# MultiSensor_MPL.net
KiCad netlist of a schematic drawn in EAGLE
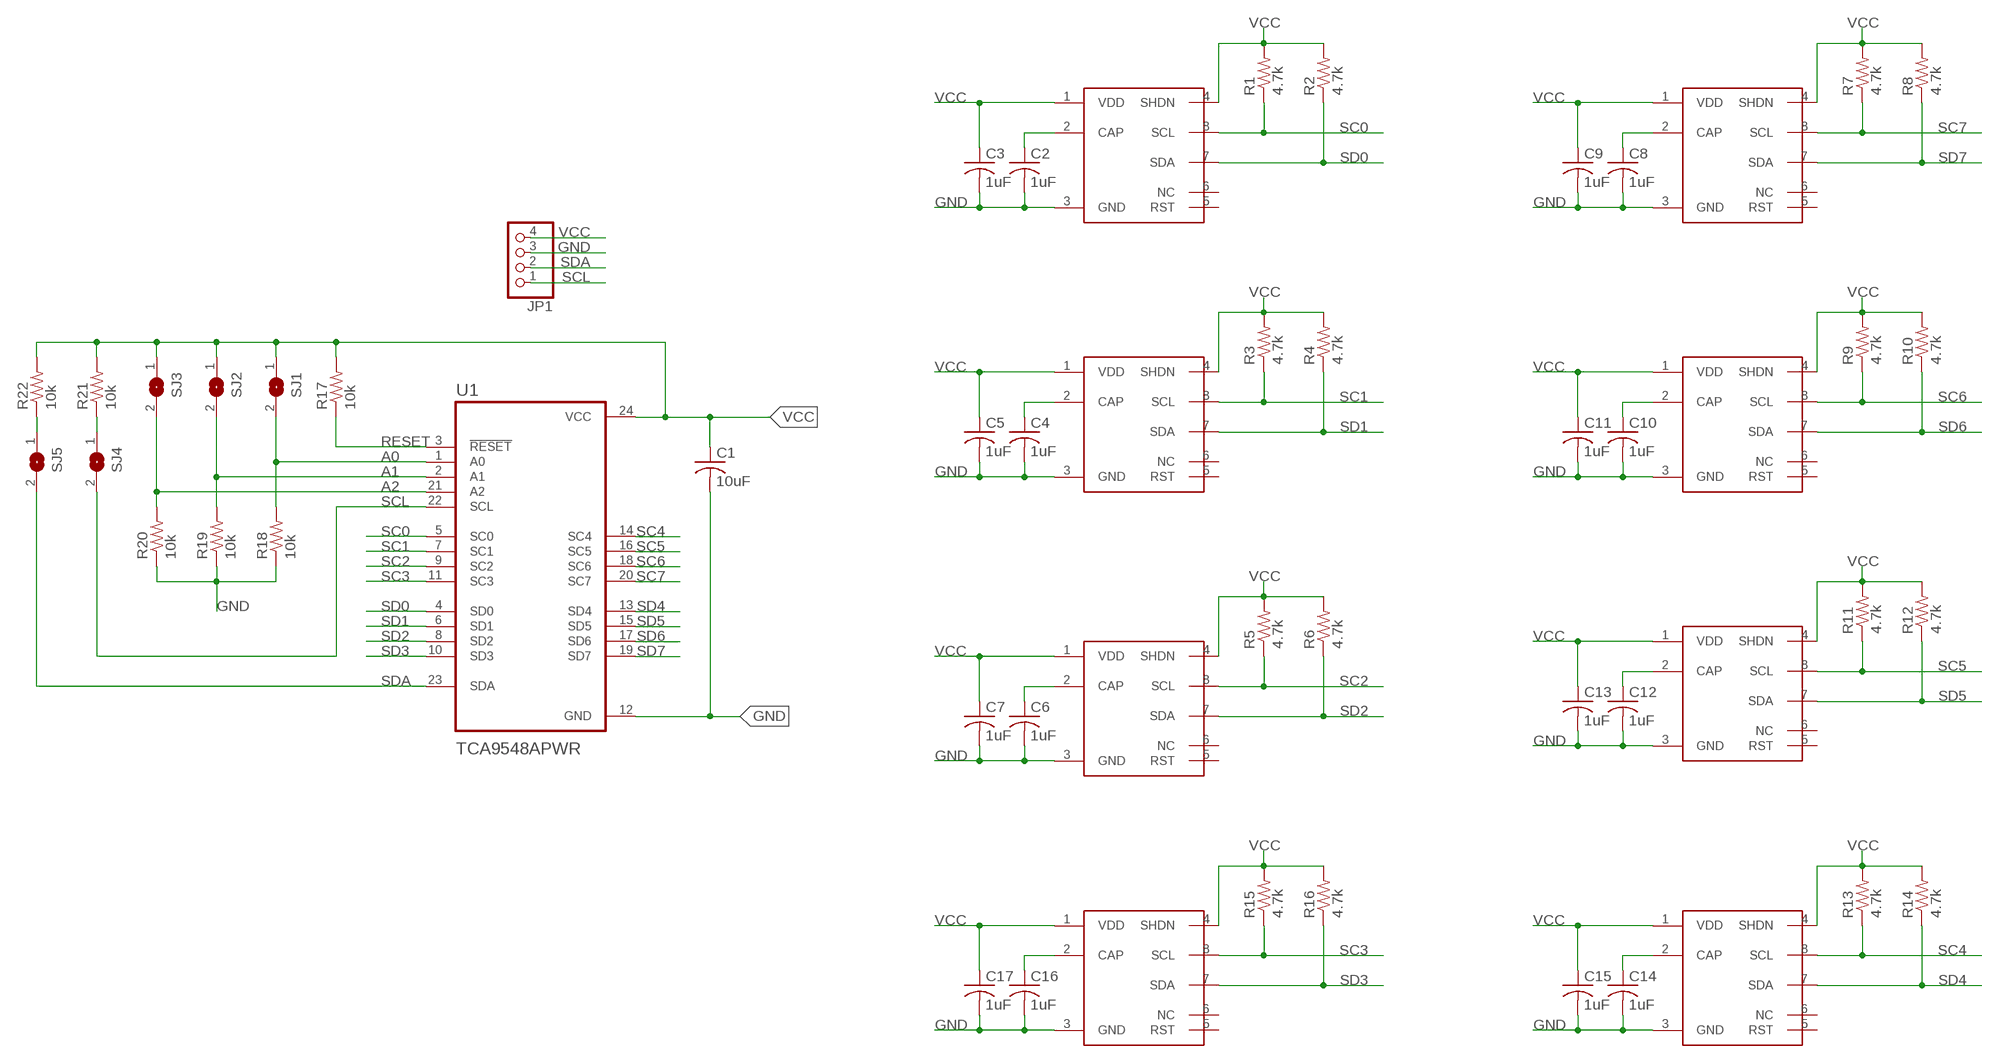
[diagram p0: schematic, sheet 1]

(export (version "E")
  (design (tool "Eeschema 10.0.6"))
  (components
    (comp (ref "B1")
      (value "MPL115A2T1")
      (footprint "eagle-import:MPL115A2T1")
      (libsource (lib "eagle-import") (part "MPL115A2T1"))
    )
    (comp (ref "B2")
      (value "MPL115A2T1")
      (footprint "eagle-import:MPL115A2T1")
      (libsource (lib "eagle-import") (part "MPL115A2T1"))
    )
    (comp (ref "B3")
      (value "MPL115A2T1")
      (footprint "eagle-import:MPL115A2T1")
      (libsource (lib "eagle-import") (part "MPL115A2T1"))
    )
    (comp (ref "B4")
      (value "MPL115A2T1")
      (footprint "eagle-import:MPL115A2T1")
      (libsource (lib "eagle-import") (part "MPL115A2T1"))
    )
    (comp (ref "B5")
      (value "MPL115A2T1")
      (footprint "eagle-import:MPL115A2T1")
      (libsource (lib "eagle-import") (part "MPL115A2T1"))
    )
    (comp (ref "B6")
      (value "MPL115A2T1")
      (footprint "eagle-import:MPL115A2T1")
      (libsource (lib "eagle-import") (part "MPL115A2T1"))
    )
    (comp (ref "B7")
      (value "MPL115A2T1")
      (footprint "eagle-import:MPL115A2T1")
      (libsource (lib "eagle-import") (part "MPL115A2T1"))
    )
    (comp (ref "B8")
      (value "MPL115A2T1")
      (footprint "eagle-import:MPL115A2T1")
      (libsource (lib "eagle-import") (part "MPL115A2T1"))
    )
    (comp (ref "C1")
      (value "10uF")
      (footprint "eagle-import:C0805")
      (libsource (lib "eagle-import") (part "C-USC0805"))
    )
    (comp (ref "C2")
      (value "1uF")
      (footprint "eagle-import:C0805")
      (libsource (lib "eagle-import") (part "C-USC0805"))
    )
    (comp (ref "C3")
      (value "1uF")
      (footprint "eagle-import:C0805")
      (libsource (lib "eagle-import") (part "C-USC0805"))
    )
    (comp (ref "C4")
      (value "1uF")
      (footprint "eagle-import:C0805")
      (libsource (lib "eagle-import") (part "C-USC0805"))
    )
    (comp (ref "C5")
      (value "1uF")
      (footprint "eagle-import:C0805")
      (libsource (lib "eagle-import") (part "C-USC0805"))
    )
    (comp (ref "C6")
      (value "1uF")
      (footprint "eagle-import:C0805")
      (libsource (lib "eagle-import") (part "C-USC0805"))
    )
    (comp (ref "C7")
      (value "1uF")
      (footprint "eagle-import:C0805")
      (libsource (lib "eagle-import") (part "C-USC0805"))
    )
    (comp (ref "C8")
      (value "1uF")
      (footprint "eagle-import:C0805")
      (libsource (lib "eagle-import") (part "C-USC0805"))
    )
    (comp (ref "C9")
      (value "1uF")
      (footprint "eagle-import:C0805")
      (libsource (lib "eagle-import") (part "C-USC0805"))
    )
    (comp (ref "C10")
      (value "1uF")
      (footprint "eagle-import:C0805")
      (libsource (lib "eagle-import") (part "C-USC0805"))
    )
    (comp (ref "C11")
      (value "1uF")
      (footprint "eagle-import:C0805")
      (libsource (lib "eagle-import") (part "C-USC0805"))
    )
    (comp (ref "C12")
      (value "1uF")
      (footprint "eagle-import:C0805")
      (libsource (lib "eagle-import") (part "C-USC0805"))
    )
    (comp (ref "C13")
      (value "1uF")
      (footprint "eagle-import:C0805")
      (libsource (lib "eagle-import") (part "C-USC0805"))
    )
    (comp (ref "C14")
      (value "1uF")
      (footprint "eagle-import:C0805")
      (libsource (lib "eagle-import") (part "C-USC0805"))
    )
    (comp (ref "C15")
      (value "1uF")
      (footprint "eagle-import:C0805")
      (libsource (lib "eagle-import") (part "C-USC0805"))
    )
    (comp (ref "C16")
      (value "1uF")
      (footprint "eagle-import:C0805")
      (libsource (lib "eagle-import") (part "C-USC0805"))
    )
    (comp (ref "C17")
      (value "1uF")
      (footprint "eagle-import:C0805")
      (libsource (lib "eagle-import") (part "C-USC0805"))
    )
    (comp (ref "JP1")
      (value "PINHD-1X4")
      (footprint "eagle-import:1X04")
      (libsource (lib "eagle-import") (part "PINHD-1X4"))
    )
    (comp (ref "R1")
      (value "4.7k")
      (footprint "eagle-import:R0805")
      (libsource (lib "eagle-import") (part "R-US_R0805"))
    )
    (comp (ref "R2")
      (value "4.7k")
      (footprint "eagle-import:R0805")
      (libsource (lib "eagle-import") (part "R-US_R0805"))
    )
    (comp (ref "R3")
      (value "4.7k")
      (footprint "eagle-import:R0805")
      (libsource (lib "eagle-import") (part "R-US_R0805"))
    )
    (comp (ref "R4")
      (value "4.7k")
      (footprint "eagle-import:R0805")
      (libsource (lib "eagle-import") (part "R-US_R0805"))
    )
    (comp (ref "R5")
      (value "4.7k")
      (footprint "eagle-import:R0805")
      (libsource (lib "eagle-import") (part "R-US_R0805"))
    )
    (comp (ref "R6")
      (value "4.7k")
      (footprint "eagle-import:R0805")
      (libsource (lib "eagle-import") (part "R-US_R0805"))
    )
    (comp (ref "R7")
      (value "4.7k")
      (footprint "eagle-import:R0805")
      (libsource (lib "eagle-import") (part "R-US_R0805"))
    )
    (comp (ref "R8")
      (value "4.7k")
      (footprint "eagle-import:R0805")
      (libsource (lib "eagle-import") (part "R-US_R0805"))
    )
    (comp (ref "R9")
      (value "4.7k")
      (footprint "eagle-import:R0805")
      (libsource (lib "eagle-import") (part "R-US_R0805"))
    )
    (comp (ref "R10")
      (value "4.7k")
      (footprint "eagle-import:R0805")
      (libsource (lib "eagle-import") (part "R-US_R0805"))
    )
    (comp (ref "R11")
      (value "4.7k")
      (footprint "eagle-import:R0805")
      (libsource (lib "eagle-import") (part "R-US_R0805"))
    )
    (comp (ref "R12")
      (value "4.7k")
      (footprint "eagle-import:R0805")
      (libsource (lib "eagle-import") (part "R-US_R0805"))
    )
    (comp (ref "R13")
      (value "4.7k")
      (footprint "eagle-import:R0805")
      (libsource (lib "eagle-import") (part "R-US_R0805"))
    )
    (comp (ref "R14")
      (value "4.7k")
      (footprint "eagle-import:R0805")
      (libsource (lib "eagle-import") (part "R-US_R0805"))
    )
    (comp (ref "R15")
      (value "4.7k")
      (footprint "eagle-import:R0805")
      (libsource (lib "eagle-import") (part "R-US_R0805"))
    )
    (comp (ref "R16")
      (value "4.7k")
      (footprint "eagle-import:R0805")
      (libsource (lib "eagle-import") (part "R-US_R0805"))
    )
    (comp (ref "R17")
      (value "10k")
      (footprint "eagle-import:R0805")
      (libsource (lib "eagle-import") (part "resistor_348_R-US_R0805"))
    )
    (comp (ref "R18")
      (value "10k")
      (footprint "eagle-import:R0805")
      (libsource (lib "eagle-import") (part "resistor_348_R-US_R0805"))
    )
    (comp (ref "R19")
      (value "10k")
      (footprint "eagle-import:R0805")
      (libsource (lib "eagle-import") (part "resistor_348_R-US_R0805"))
    )
    (comp (ref "R20")
      (value "10k")
      (footprint "eagle-import:R0805")
      (libsource (lib "eagle-import") (part "resistor_348_R-US_R0805"))
    )
    (comp (ref "R21")
      (value "10k")
      (footprint "eagle-import:R0805")
      (libsource (lib "eagle-import") (part "resistor_348_R-US_R0805"))
    )
    (comp (ref "R22")
      (value "10k")
      (footprint "eagle-import:R0805")
      (libsource (lib "eagle-import") (part "resistor_348_R-US_R0805"))
    )
    (comp (ref "SJ1") (value "SJ") (footprint "eagle-import:SJ") (libsource (lib "eagle-import") (part "SJ")))
    (comp (ref "SJ2") (value "SJ") (footprint "eagle-import:SJ") (libsource (lib "eagle-import") (part "SJ")))
    (comp (ref "SJ3") (value "SJ") (footprint "eagle-import:SJ") (libsource (lib "eagle-import") (part "SJ")))
    (comp (ref "SJ4") (value "SJ") (footprint "eagle-import:SJ") (libsource (lib "eagle-import") (part "SJ")))
    (comp (ref "SJ5") (value "SJ") (footprint "eagle-import:SJ") (libsource (lib "eagle-import") (part "SJ")))
    (comp (ref "U1")
      (value "TCA9548APWR")
      (footprint "eagle-import:SOP65P640X120-24N")
      (fields (field (name "DIGI-KEY_PART_NUMBER") "296-34905-1-ND") (field (name "MF") "Texas Instruments"))
      (libsource (lib "eagle-import") (part "TCA9548APWR"))
    )
  )
  (nets
    (net (code "1") (name "/A0") (class "Default")
      (node (ref "R18") (pin "2") (pinfunction "2_2") (pintype "passive"))
      (node (ref "SJ1") (pin "2") (pinfunction "2_2") (pintype "passive"))
      (node (ref "U1") (pin "1") (pinfunction "A0_1") (pintype "input"))
    )
    (net (code "2") (name "/A1") (class "Default")
      (node (ref "R19") (pin "2") (pinfunction "2_2") (pintype "passive"))
      (node (ref "SJ2") (pin "2") (pinfunction "2_2") (pintype "passive"))
      (node (ref "U1") (pin "2") (pinfunction "A1_2") (pintype "input"))
    )
    (net (code "3") (name "/A2") (class "Default")
      (node (ref "R20") (pin "2") (pinfunction "2_2") (pintype "passive"))
      (node (ref "SJ3") (pin "2") (pinfunction "2_2") (pintype "passive"))
      (node (ref "U1") (pin "21") (pinfunction "A2_21") (pintype "input"))
    )
    (net (code "4") (name "/RESET") (class "Default")
      (node (ref "R17") (pin "1") (pinfunction "1_1") (pintype "passive"))
      (node (ref "U1") (pin "3") (pinfunction "~{RESET}_3") (pintype "input"))
    )
    (net (code "5") (name "/SC0") (class "Default")
      (node (ref "B1") (pin "8") (pinfunction "SCL_8") (pintype "bidirectional"))
      (node (ref "R1") (pin "1") (pinfunction "1_1") (pintype "passive"))
      (node (ref "U1") (pin "5") (pinfunction "SC0_5") (pintype "bidirectional"))
    )
    (net (code "6") (name "/SC1") (class "Default")
      (node (ref "B2") (pin "8") (pinfunction "SCL_8") (pintype "bidirectional"))
      (node (ref "R3") (pin "1") (pinfunction "1_1") (pintype "passive"))
      (node (ref "U1") (pin "7") (pinfunction "SC1_7") (pintype "bidirectional"))
    )
    (net (code "7") (name "/SC2") (class "Default")
      (node (ref "B3") (pin "8") (pinfunction "SCL_8") (pintype "bidirectional"))
      (node (ref "R5") (pin "1") (pinfunction "1_1") (pintype "passive"))
      (node (ref "U1") (pin "9") (pinfunction "SC2_9") (pintype "bidirectional"))
    )
    (net (code "8") (name "/SC3") (class "Default")
      (node (ref "B8") (pin "8") (pinfunction "SCL_8") (pintype "bidirectional"))
      (node (ref "R15") (pin "1") (pinfunction "1_1") (pintype "passive"))
      (node (ref "U1") (pin "11") (pinfunction "SC3_11") (pintype "bidirectional"))
    )
    (net (code "9") (name "/SC4") (class "Default")
      (node (ref "B7") (pin "8") (pinfunction "SCL_8") (pintype "bidirectional"))
      (node (ref "R13") (pin "1") (pinfunction "1_1") (pintype "passive"))
      (node (ref "U1") (pin "14") (pinfunction "SC4_14") (pintype "bidirectional"))
    )
    (net (code "10") (name "/SC5") (class "Default")
      (node (ref "B6") (pin "8") (pinfunction "SCL_8") (pintype "bidirectional"))
      (node (ref "R11") (pin "1") (pinfunction "1_1") (pintype "passive"))
      (node (ref "U1") (pin "16") (pinfunction "SC5_16") (pintype "bidirectional"))
    )
    (net (code "11") (name "/SC6") (class "Default")
      (node (ref "B5") (pin "8") (pinfunction "SCL_8") (pintype "bidirectional"))
      (node (ref "R9") (pin "1") (pinfunction "1_1") (pintype "passive"))
      (node (ref "U1") (pin "18") (pinfunction "SC6_18") (pintype "bidirectional"))
    )
    (net (code "12") (name "/SC7") (class "Default")
      (node (ref "B4") (pin "8") (pinfunction "SCL_8") (pintype "bidirectional"))
      (node (ref "R7") (pin "1") (pinfunction "1_1") (pintype "passive"))
      (node (ref "U1") (pin "20") (pinfunction "SC7_20") (pintype "bidirectional"))
    )
    (net (code "13") (name "/SCL") (class "Default")
      (node (ref "JP1") (pin "1") (pinfunction "1_1") (pintype "passive"))
      (node (ref "SJ4") (pin "2") (pinfunction "2_2") (pintype "passive"))
      (node (ref "U1") (pin "22") (pinfunction "SCL_22") (pintype "input"))
    )
    (net (code "14") (name "/SD0") (class "Default")
      (node (ref "B1") (pin "7") (pinfunction "SDA_7") (pintype "bidirectional"))
      (node (ref "R2") (pin "1") (pinfunction "1_1") (pintype "passive"))
      (node (ref "U1") (pin "4") (pinfunction "SD0_4") (pintype "bidirectional"))
    )
    (net (code "15") (name "/SD1") (class "Default")
      (node (ref "B2") (pin "7") (pinfunction "SDA_7") (pintype "bidirectional"))
      (node (ref "R4") (pin "1") (pinfunction "1_1") (pintype "passive"))
      (node (ref "U1") (pin "6") (pinfunction "SD1_6") (pintype "bidirectional"))
    )
    (net (code "16") (name "/SD2") (class "Default")
      (node (ref "B3") (pin "7") (pinfunction "SDA_7") (pintype "bidirectional"))
      (node (ref "R6") (pin "1") (pinfunction "1_1") (pintype "passive"))
      (node (ref "U1") (pin "8") (pinfunction "SD2_8") (pintype "bidirectional"))
    )
    (net (code "17") (name "/SD3") (class "Default")
      (node (ref "B8") (pin "7") (pinfunction "SDA_7") (pintype "bidirectional"))
      (node (ref "R16") (pin "1") (pinfunction "1_1") (pintype "passive"))
      (node (ref "U1") (pin "10") (pinfunction "SD3_10") (pintype "bidirectional"))
    )
    (net (code "18") (name "/SD4") (class "Default")
      (node (ref "B7") (pin "7") (pinfunction "SDA_7") (pintype "bidirectional"))
      (node (ref "R14") (pin "1") (pinfunction "1_1") (pintype "passive"))
      (node (ref "U1") (pin "13") (pinfunction "SD4_13") (pintype "bidirectional"))
    )
    (net (code "19") (name "/SD5") (class "Default")
      (node (ref "B6") (pin "7") (pinfunction "SDA_7") (pintype "bidirectional"))
      (node (ref "R12") (pin "1") (pinfunction "1_1") (pintype "passive"))
      (node (ref "U1") (pin "15") (pinfunction "SD5_15") (pintype "bidirectional"))
    )
    (net (code "20") (name "/SD6") (class "Default")
      (node (ref "B5") (pin "7") (pinfunction "SDA_7") (pintype "bidirectional"))
      (node (ref "R10") (pin "1") (pinfunction "1_1") (pintype "passive"))
      (node (ref "U1") (pin "17") (pinfunction "SD6_17") (pintype "bidirectional"))
    )
    (net (code "21") (name "/SD7") (class "Default")
      (node (ref "B4") (pin "7") (pinfunction "SDA_7") (pintype "bidirectional"))
      (node (ref "R8") (pin "1") (pinfunction "1_1") (pintype "passive"))
      (node (ref "U1") (pin "19") (pinfunction "SD7_19") (pintype "bidirectional"))
    )
    (net (code "22") (name "/SDA") (class "Default")
      (node (ref "JP1") (pin "2") (pinfunction "2_2") (pintype "passive"))
      (node (ref "SJ5") (pin "2") (pinfunction "2_2") (pintype "passive"))
      (node (ref "U1") (pin "23") (pinfunction "SDA_23") (pintype "bidirectional"))
    )
    (net (code "23") (name "GND") (class "Default")
      (node (ref "B1") (pin "3") (pinfunction "GND_3") (pintype "bidirectional"))
      (node (ref "B2") (pin "3") (pinfunction "GND_3") (pintype "bidirectional"))
      (node (ref "B3") (pin "3") (pinfunction "GND_3") (pintype "bidirectional"))
      (node (ref "B4") (pin "3") (pinfunction "GND_3") (pintype "bidirectional"))
      (node (ref "B5") (pin "3") (pinfunction "GND_3") (pintype "bidirectional"))
      (node (ref "B6") (pin "3") (pinfunction "GND_3") (pintype "bidirectional"))
      (node (ref "B7") (pin "3") (pinfunction "GND_3") (pintype "bidirectional"))
      (node (ref "B8") (pin "3") (pinfunction "GND_3") (pintype "bidirectional"))
      (node (ref "C1") (pin "2") (pinfunction "2_2") (pintype "passive"))
      (node (ref "C10") (pin "2") (pinfunction "2_2") (pintype "passive"))
      (node (ref "C11") (pin "2") (pinfunction "2_2") (pintype "passive"))
      (node (ref "C12") (pin "2") (pinfunction "2_2") (pintype "passive"))
      (node (ref "C13") (pin "2") (pinfunction "2_2") (pintype "passive"))
      (node (ref "C14") (pin "2") (pinfunction "2_2") (pintype "passive"))
      (node (ref "C15") (pin "2") (pinfunction "2_2") (pintype "passive"))
      (node (ref "C16") (pin "2") (pinfunction "2_2") (pintype "passive"))
      (node (ref "C17") (pin "2") (pinfunction "2_2") (pintype "passive"))
      (node (ref "C2") (pin "2") (pinfunction "2_2") (pintype "passive"))
      (node (ref "C3") (pin "2") (pinfunction "2_2") (pintype "passive"))
      (node (ref "C4") (pin "2") (pinfunction "2_2") (pintype "passive"))
      (node (ref "C5") (pin "2") (pinfunction "2_2") (pintype "passive"))
      (node (ref "C6") (pin "2") (pinfunction "2_2") (pintype "passive"))
      (node (ref "C7") (pin "2") (pinfunction "2_2") (pintype "passive"))
      (node (ref "C8") (pin "2") (pinfunction "2_2") (pintype "passive"))
      (node (ref "C9") (pin "2") (pinfunction "2_2") (pintype "passive"))
      (node (ref "JP1") (pin "3") (pinfunction "3_3") (pintype "passive"))
      (node (ref "R18") (pin "1") (pinfunction "1_1") (pintype "passive"))
      (node (ref "R19") (pin "1") (pinfunction "1_1") (pintype "passive"))
      (node (ref "R20") (pin "1") (pinfunction "1_1") (pintype "passive"))
      (node (ref "U1") (pin "12") (pinfunction "GND_12") (pintype "power_in"))
    )
    (net (code "24") (name "Net-(B1-CAP)") (class "Default")
      (node (ref "B1") (pin "2") (pinfunction "CAP_2") (pintype "bidirectional"))
      (node (ref "C2") (pin "1") (pinfunction "1_1") (pintype "passive"))
    )
    (net (code "25") (name "Net-(B2-CAP)") (class "Default")
      (node (ref "B2") (pin "2") (pinfunction "CAP_2") (pintype "bidirectional"))
      (node (ref "C4") (pin "1") (pinfunction "1_1") (pintype "passive"))
    )
    (net (code "26") (name "Net-(B3-CAP)") (class "Default")
      (node (ref "B3") (pin "2") (pinfunction "CAP_2") (pintype "bidirectional"))
      (node (ref "C6") (pin "1") (pinfunction "1_1") (pintype "passive"))
    )
    (net (code "27") (name "Net-(B4-CAP)") (class "Default")
      (node (ref "B4") (pin "2") (pinfunction "CAP_2") (pintype "bidirectional"))
      (node (ref "C8") (pin "1") (pinfunction "1_1") (pintype "passive"))
    )
    (net (code "28") (name "Net-(B5-CAP)") (class "Default")
      (node (ref "B5") (pin "2") (pinfunction "CAP_2") (pintype "bidirectional"))
      (node (ref "C10") (pin "1") (pinfunction "1_1") (pintype "passive"))
    )
    (net (code "29") (name "Net-(B6-CAP)") (class "Default")
      (node (ref "B6") (pin "2") (pinfunction "CAP_2") (pintype "bidirectional"))
      (node (ref "C12") (pin "1") (pinfunction "1_1") (pintype "passive"))
    )
    (net (code "30") (name "Net-(B7-CAP)") (class "Default")
      (node (ref "B7") (pin "2") (pinfunction "CAP_2") (pintype "bidirectional"))
      (node (ref "C14") (pin "1") (pinfunction "1_1") (pintype "passive"))
    )
    (net (code "31") (name "Net-(B8-CAP)") (class "Default")
      (node (ref "B8") (pin "2") (pinfunction "CAP_2") (pintype "bidirectional"))
      (node (ref "C16") (pin "1") (pinfunction "1_1") (pintype "passive"))
    )
    (net (code "32") (name "Net-(R21-Pad1)") (class "Default")
      (node (ref "R21") (pin "1") (pinfunction "1_1") (pintype "passive"))
      (node (ref "SJ4") (pin "1") (pinfunction "1_1") (pintype "passive"))
    )
    (net (code "33") (name "Net-(R22-Pad1)") (class "Default")
      (node (ref "R22") (pin "1") (pinfunction "1_1") (pintype "passive"))
      (node (ref "SJ5") (pin "1") (pinfunction "1_1") (pintype "passive"))
    )
    (net (code "34") (name "VCC") (class "Default")
      (node (ref "B1") (pin "1") (pinfunction "VDD_1") (pintype "bidirectional"))
      (node (ref "B1") (pin "4") (pinfunction "SHDN_4") (pintype "bidirectional"))
      (node (ref "B2") (pin "1") (pinfunction "VDD_1") (pintype "bidirectional"))
      (node (ref "B2") (pin "4") (pinfunction "SHDN_4") (pintype "bidirectional"))
      (node (ref "B3") (pin "1") (pinfunction "VDD_1") (pintype "bidirectional"))
      (node (ref "B3") (pin "4") (pinfunction "SHDN_4") (pintype "bidirectional"))
      (node (ref "B4") (pin "1") (pinfunction "VDD_1") (pintype "bidirectional"))
      (node (ref "B4") (pin "4") (pinfunction "SHDN_4") (pintype "bidirectional"))
      (node (ref "B5") (pin "1") (pinfunction "VDD_1") (pintype "bidirectional"))
      (node (ref "B5") (pin "4") (pinfunction "SHDN_4") (pintype "bidirectional"))
      (node (ref "B6") (pin "1") (pinfunction "VDD_1") (pintype "bidirectional"))
      (node (ref "B6") (pin "4") (pinfunction "SHDN_4") (pintype "bidirectional"))
      (node (ref "B7") (pin "1") (pinfunction "VDD_1") (pintype "bidirectional"))
      (node (ref "B7") (pin "4") (pinfunction "SHDN_4") (pintype "bidirectional"))
      (node (ref "B8") (pin "1") (pinfunction "VDD_1") (pintype "bidirectional"))
      (node (ref "B8") (pin "4") (pinfunction "SHDN_4") (pintype "bidirectional"))
      (node (ref "C1") (pin "1") (pinfunction "1_1") (pintype "passive"))
      (node (ref "C11") (pin "1") (pinfunction "1_1") (pintype "passive"))
      (node (ref "C13") (pin "1") (pinfunction "1_1") (pintype "passive"))
      (node (ref "C15") (pin "1") (pinfunction "1_1") (pintype "passive"))
      (node (ref "C17") (pin "1") (pinfunction "1_1") (pintype "passive"))
      (node (ref "C3") (pin "1") (pinfunction "1_1") (pintype "passive"))
      (node (ref "C5") (pin "1") (pinfunction "1_1") (pintype "passive"))
      (node (ref "C7") (pin "1") (pinfunction "1_1") (pintype "passive"))
      (node (ref "C9") (pin "1") (pinfunction "1_1") (pintype "passive"))
      (node (ref "JP1") (pin "4") (pinfunction "4_4") (pintype "passive"))
      (node (ref "R1") (pin "2") (pinfunction "2_2") (pintype "passive"))
      (node (ref "R10") (pin "2") (pinfunction "2_2") (pintype "passive"))
      (node (ref "R11") (pin "2") (pinfunction "2_2") (pintype "passive"))
      (node (ref "R12") (pin "2") (pinfunction "2_2") (pintype "passive"))
      (node (ref "R13") (pin "2") (pinfunction "2_2") (pintype "passive"))
      (node (ref "R14") (pin "2") (pinfunction "2_2") (pintype "passive"))
      (node (ref "R15") (pin "2") (pinfunction "2_2") (pintype "passive"))
      (node (ref "R16") (pin "2") (pinfunction "2_2") (pintype "passive"))
      (node (ref "R17") (pin "2") (pinfunction "2_2") (pintype "passive"))
      (node (ref "R2") (pin "2") (pinfunction "2_2") (pintype "passive"))
      (node (ref "R21") (pin "2") (pinfunction "2_2") (pintype "passive"))
      (node (ref "R22") (pin "2") (pinfunction "2_2") (pintype "passive"))
      (node (ref "R3") (pin "2") (pinfunction "2_2") (pintype "passive"))
      (node (ref "R4") (pin "2") (pinfunction "2_2") (pintype "passive"))
      (node (ref "R5") (pin "2") (pinfunction "2_2") (pintype "passive"))
      (node (ref "R6") (pin "2") (pinfunction "2_2") (pintype "passive"))
      (node (ref "R7") (pin "2") (pinfunction "2_2") (pintype "passive"))
      (node (ref "R8") (pin "2") (pinfunction "2_2") (pintype "passive"))
      (node (ref "R9") (pin "2") (pinfunction "2_2") (pintype "passive"))
      (node (ref "SJ1") (pin "1") (pinfunction "1_1") (pintype "passive"))
      (node (ref "SJ2") (pin "1") (pinfunction "1_1") (pintype "passive"))
      (node (ref "SJ3") (pin "1") (pinfunction "1_1") (pintype "passive"))
      (node (ref "U1") (pin "24") (pinfunction "VCC_24") (pintype "power_in"))
    )
    (net (code "35") (name "unconnected-(B1-NC-Pad6)") (class "Default")
      (node (ref "B1") (pin "6") (pinfunction "NC_6") (pintype "bidirectional"))
    )
    (net (code "36") (name "unconnected-(B1-RST-Pad5)") (class "Default")
      (node (ref "B1") (pin "5") (pinfunction "RST_5") (pintype "bidirectional"))
    )
    (net (code "37") (name "unconnected-(B2-NC-Pad6)") (class "Default")
      (node (ref "B2") (pin "6") (pinfunction "NC_6") (pintype "bidirectional"))
    )
    (net (code "38") (name "unconnected-(B2-RST-Pad5)") (class "Default")
      (node (ref "B2") (pin "5") (pinfunction "RST_5") (pintype "bidirectional"))
    )
    (net (code "39") (name "unconnected-(B3-NC-Pad6)") (class "Default")
      (node (ref "B3") (pin "6") (pinfunction "NC_6") (pintype "bidirectional"))
    )
    (net (code "40") (name "unconnected-(B3-RST-Pad5)") (class "Default")
      (node (ref "B3") (pin "5") (pinfunction "RST_5") (pintype "bidirectional"))
    )
    (net (code "41") (name "unconnected-(B4-NC-Pad6)") (class "Default")
      (node (ref "B4") (pin "6") (pinfunction "NC_6") (pintype "bidirectional"))
    )
    (net (code "42") (name "unconnected-(B4-RST-Pad5)") (class "Default")
      (node (ref "B4") (pin "5") (pinfunction "RST_5") (pintype "bidirectional"))
    )
    (net (code "43") (name "unconnected-(B5-NC-Pad6)") (class "Default")
      (node (ref "B5") (pin "6") (pinfunction "NC_6") (pintype "bidirectional"))
    )
    (net (code "44") (name "unconnected-(B5-RST-Pad5)") (class "Default")
      (node (ref "B5") (pin "5") (pinfunction "RST_5") (pintype "bidirectional"))
    )
    (net (code "45") (name "unconnected-(B6-NC-Pad6)") (class "Default")
      (node (ref "B6") (pin "6") (pinfunction "NC_6") (pintype "bidirectional"))
    )
    (net (code "46") (name "unconnected-(B6-RST-Pad5)") (class "Default")
      (node (ref "B6") (pin "5") (pinfunction "RST_5") (pintype "bidirectional"))
    )
    (net (code "47") (name "unconnected-(B7-NC-Pad6)") (class "Default")
      (node (ref "B7") (pin "6") (pinfunction "NC_6") (pintype "bidirectional"))
    )
    (net (code "48") (name "unconnected-(B7-RST-Pad5)") (class "Default")
      (node (ref "B7") (pin "5") (pinfunction "RST_5") (pintype "bidirectional"))
    )
    (net (code "49") (name "unconnected-(B8-NC-Pad6)") (class "Default")
      (node (ref "B8") (pin "6") (pinfunction "NC_6") (pintype "bidirectional"))
    )
    (net (code "50") (name "unconnected-(B8-RST-Pad5)") (class "Default")
      (node (ref "B8") (pin "5") (pinfunction "RST_5") (pintype "bidirectional"))
    )
  )
)
